# ENC_1_1.net
KiCad netlist of a schematic drawn in EAGLE
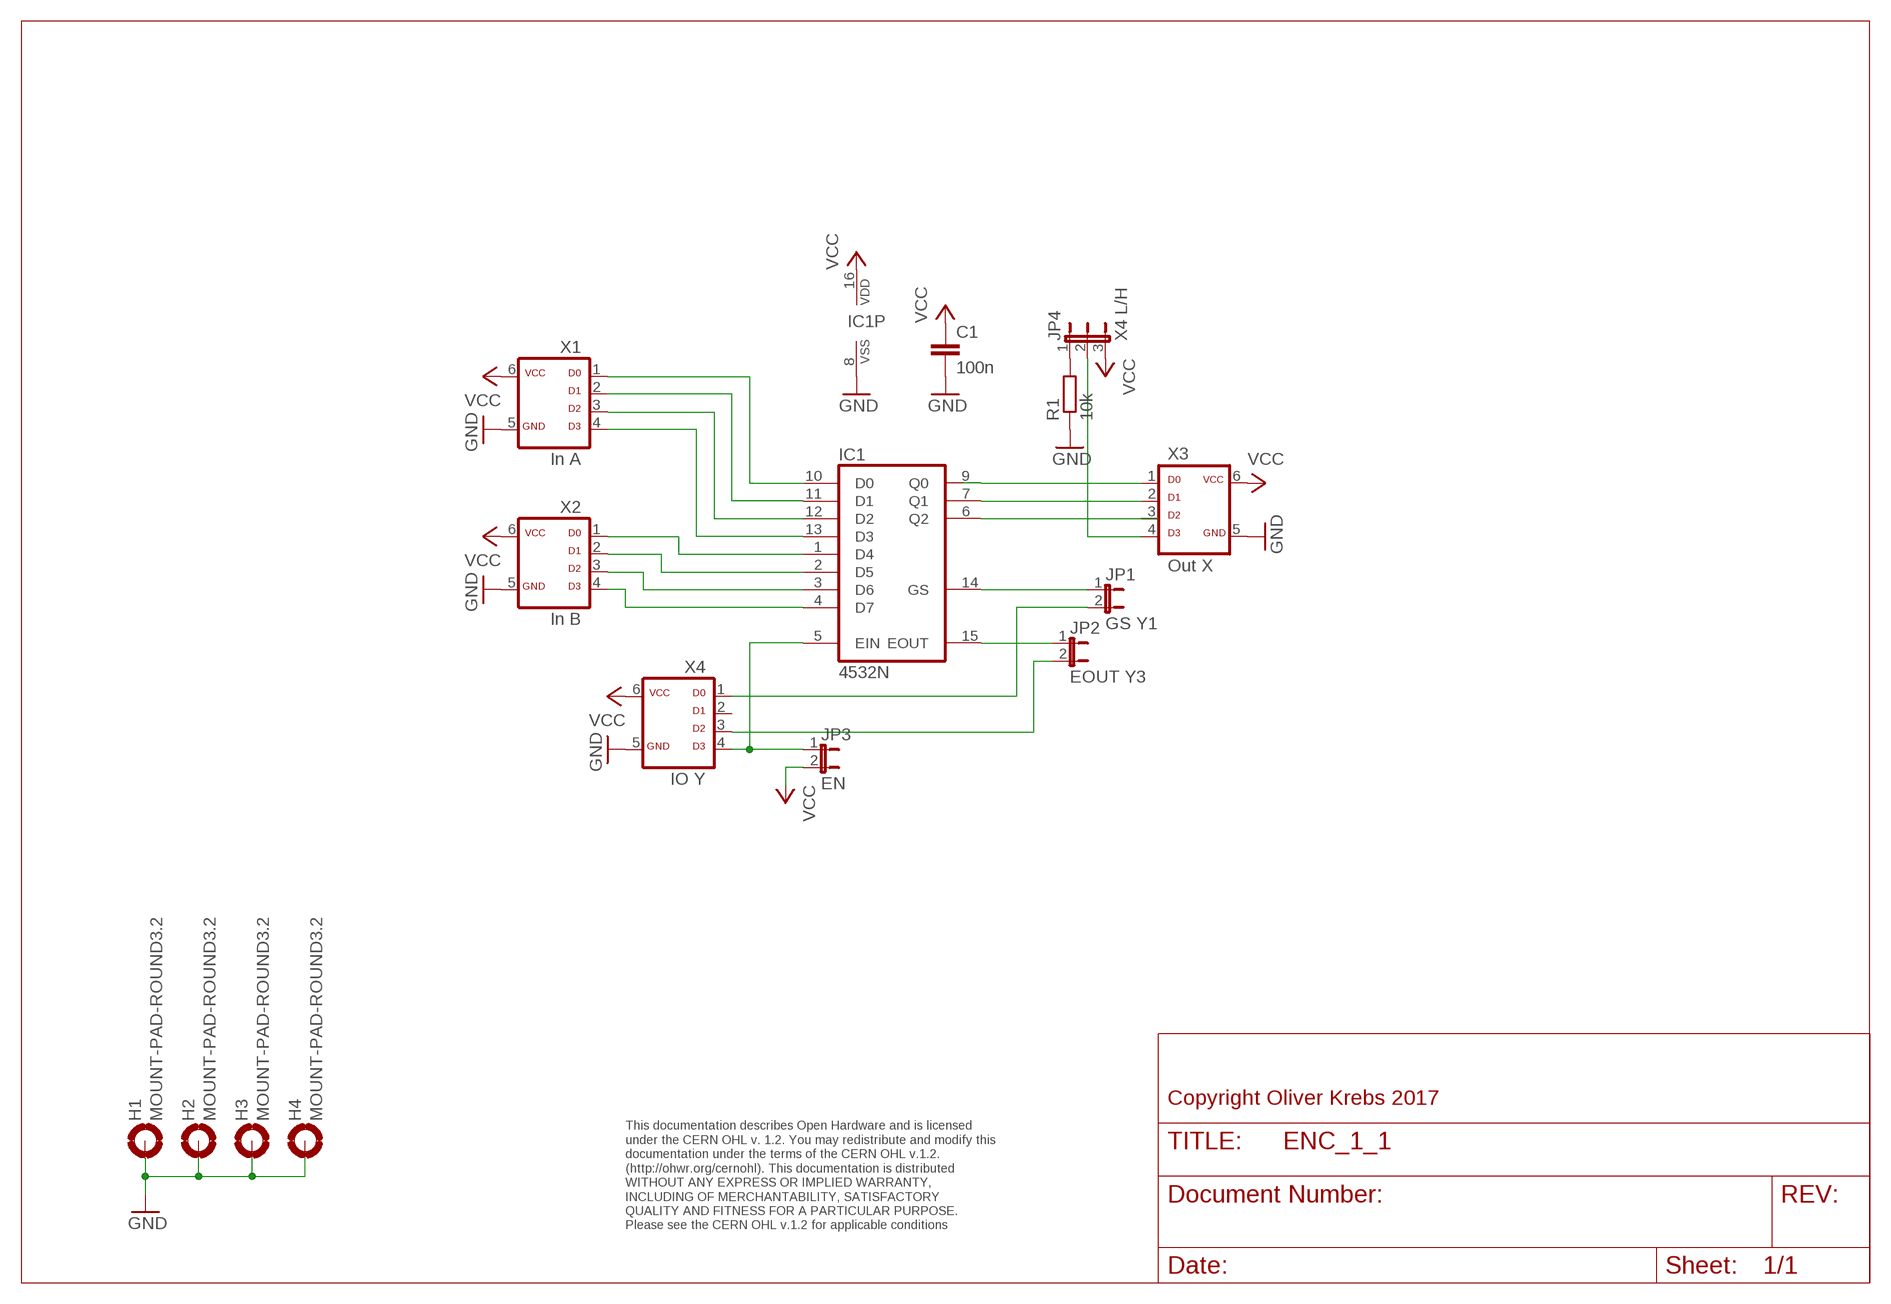
[diagram p0: schematic, sheet 1]

(export (version "E")
  (design (tool "Eeschema 10.0.6"))
  (components
    (comp (ref "C1")
      (value "100n")
      (footprint "eagle-import:C050-025X075")
      (libsource (lib "eagle-import") (part "C-EU050-025X075"))
    )
    (comp (ref "H1")
      (value "MOUNT-PAD-ROUND3.2")
      (footprint "eagle-import:3,2-PAD")
      (libsource (lib "eagle-import") (part "MOUNT-PAD-ROUND3.2"))
    )
    (comp (ref "H2")
      (value "MOUNT-PAD-ROUND3.2")
      (footprint "eagle-import:3,2-PAD")
      (libsource (lib "eagle-import") (part "MOUNT-PAD-ROUND3.2"))
    )
    (comp (ref "H3")
      (value "MOUNT-PAD-ROUND3.2")
      (footprint "eagle-import:3,2-PAD")
      (libsource (lib "eagle-import") (part "MOUNT-PAD-ROUND3.2"))
    )
    (comp (ref "H4")
      (value "MOUNT-PAD-ROUND3.2")
      (footprint "eagle-import:3,2-PAD")
      (libsource (lib "eagle-import") (part "MOUNT-PAD-ROUND3.2"))
    )
    (comp (ref "IC1")
      (value "4532N")
      (footprint "eagle-import:DIL16")
      (libsource (lib "eagle-import") (part "4532N"))
    )
    (comp (ref "JP1")
      (value "GS Y1")
      (footprint "eagle-import:JP1")
      (libsource (lib "eagle-import") (part "JP1E"))
    )
    (comp (ref "JP2")
      (value "EOUT Y3")
      (footprint "eagle-import:JP1")
      (libsource (lib "eagle-import") (part "JP1E"))
    )
    (comp (ref "JP3")
      (value "EN")
      (footprint "eagle-import:JP1")
      (libsource (lib "eagle-import") (part "JP1E"))
    )
    (comp (ref "JP4")
      (value "X4 L/H")
      (footprint "eagle-import:JP2-U")
      (libsource (lib "eagle-import") (part "JP2EJP2-U"))
    )
    (comp (ref "R1")
      (value "10k")
      (footprint "eagle-import:0207_10")
      (libsource (lib "eagle-import") (part "R-EU_0207/10"))
    )
    (comp (ref "X1")
      (value "In A")
      (footprint "eagle-import:ML-6")
      (libsource (lib "eagle-import") (part "ML6D"))
    )
    (comp (ref "X2")
      (value "In B")
      (footprint "eagle-import:ML-6")
      (libsource (lib "eagle-import") (part "ML6D"))
    )
    (comp (ref "X3")
      (value "Out X")
      (footprint "eagle-import:ML-6")
      (libsource (lib "eagle-import") (part "ML6D"))
    )
    (comp (ref "X4")
      (value "IO Y")
      (footprint "eagle-import:ML-6")
      (libsource (lib "eagle-import") (part "ML6D"))
    )
  )
  (nets
    (net (code "1") (name "GND") (class "Default")
      (node (ref "C1") (pin "2") (pinfunction "2_2") (pintype "passive"))
      (node (ref "H1") (pin "B3,2") (pinfunction "MOUNT_B3,2") (pintype "passive"))
      (node (ref "H2") (pin "B3,2") (pinfunction "MOUNT_B3,2") (pintype "passive"))
      (node (ref "H3") (pin "B3,2") (pinfunction "MOUNT_B3,2") (pintype "passive"))
      (node (ref "H4") (pin "B3,2") (pinfunction "MOUNT_B3,2") (pintype "passive"))
      (node (ref "IC1") (pin "8") (pinfunction "VSS_8") (pintype "power_in"))
      (node (ref "R1") (pin "1") (pinfunction "1_1") (pintype "passive"))
      (node (ref "X1") (pin "5") (pinfunction "5_5") (pintype "passive"))
      (node (ref "X2") (pin "5") (pinfunction "5_5") (pintype "passive"))
      (node (ref "X3") (pin "5") (pinfunction "5_5") (pintype "passive"))
      (node (ref "X4") (pin "5") (pinfunction "5_5") (pintype "passive"))
    )
    (net (code "2") (name "Net-(IC1A-D0)") (class "Default")
      (node (ref "IC1") (pin "10") (pinfunction "D0_10") (pintype "input"))
      (node (ref "X1") (pin "1") (pinfunction "1_1") (pintype "passive"))
    )
    (net (code "3") (name "Net-(IC1A-D1)") (class "Default")
      (node (ref "IC1") (pin "11") (pinfunction "D1_11") (pintype "input"))
      (node (ref "X1") (pin "2") (pinfunction "2_2") (pintype "passive"))
    )
    (net (code "4") (name "Net-(IC1A-D2)") (class "Default")
      (node (ref "IC1") (pin "12") (pinfunction "D2_12") (pintype "input"))
      (node (ref "X1") (pin "3") (pinfunction "3_3") (pintype "passive"))
    )
    (net (code "5") (name "Net-(IC1A-D3)") (class "Default")
      (node (ref "IC1") (pin "13") (pinfunction "D3_13") (pintype "input"))
      (node (ref "X1") (pin "4") (pinfunction "4_4") (pintype "passive"))
    )
    (net (code "6") (name "Net-(IC1A-D4)") (class "Default")
      (node (ref "IC1") (pin "1") (pinfunction "D4_1") (pintype "input"))
      (node (ref "X2") (pin "1") (pinfunction "1_1") (pintype "passive"))
    )
    (net (code "7") (name "Net-(IC1A-D5)") (class "Default")
      (node (ref "IC1") (pin "2") (pinfunction "D5_2") (pintype "input"))
      (node (ref "X2") (pin "2") (pinfunction "2_2") (pintype "passive"))
    )
    (net (code "8") (name "Net-(IC1A-D6)") (class "Default")
      (node (ref "IC1") (pin "3") (pinfunction "D6_3") (pintype "input"))
      (node (ref "X2") (pin "3") (pinfunction "3_3") (pintype "passive"))
    )
    (net (code "9") (name "Net-(IC1A-D7)") (class "Default")
      (node (ref "IC1") (pin "4") (pinfunction "D7_4") (pintype "input"))
      (node (ref "X2") (pin "4") (pinfunction "4_4") (pintype "passive"))
    )
    (net (code "10") (name "Net-(IC1A-EIN)") (class "Default")
      (node (ref "IC1") (pin "5") (pinfunction "EIN_5") (pintype "input"))
      (node (ref "JP3") (pin "1") (pinfunction "1_1") (pintype "passive"))
      (node (ref "X4") (pin "4") (pinfunction "4_4") (pintype "passive"))
    )
    (net (code "11") (name "Net-(IC1A-EOUT)") (class "Default")
      (node (ref "IC1") (pin "15") (pinfunction "EOUT_15") (pintype "output"))
      (node (ref "JP2") (pin "1") (pinfunction "1_1") (pintype "passive"))
    )
    (net (code "12") (name "Net-(IC1A-GS)") (class "Default")
      (node (ref "IC1") (pin "14") (pinfunction "GS_14") (pintype "output"))
      (node (ref "JP1") (pin "1") (pinfunction "1_1") (pintype "passive"))
    )
    (net (code "13") (name "Net-(IC1A-Q0)") (class "Default")
      (node (ref "IC1") (pin "9") (pinfunction "Q0_9") (pintype "output"))
      (node (ref "X3") (pin "1") (pinfunction "1_1") (pintype "passive"))
    )
    (net (code "14") (name "Net-(IC1A-Q1)") (class "Default")
      (node (ref "IC1") (pin "7") (pinfunction "Q1_7") (pintype "output"))
      (node (ref "X3") (pin "2") (pinfunction "2_2") (pintype "passive"))
    )
    (net (code "15") (name "Net-(IC1A-Q2)") (class "Default")
      (node (ref "IC1") (pin "6") (pinfunction "Q2_6") (pintype "output"))
      (node (ref "X3") (pin "3") (pinfunction "3_3") (pintype "passive"))
    )
    (net (code "16") (name "Net-(JP1-Pad2)") (class "Default")
      (node (ref "JP1") (pin "2") (pinfunction "2_2") (pintype "passive"))
      (node (ref "X4") (pin "1") (pinfunction "1_1") (pintype "passive"))
    )
    (net (code "17") (name "Net-(JP2-Pad2)") (class "Default")
      (node (ref "JP2") (pin "2") (pinfunction "2_2") (pintype "passive"))
      (node (ref "X4") (pin "3") (pinfunction "3_3") (pintype "passive"))
    )
    (net (code "18") (name "Net-(JP4-Pad1)") (class "Default")
      (node (ref "JP4") (pin "1") (pinfunction "1_1") (pintype "passive"))
      (node (ref "R1") (pin "2") (pinfunction "2_2") (pintype "passive"))
    )
    (net (code "19") (name "Net-(JP4-Pad2)") (class "Default")
      (node (ref "JP4") (pin "2") (pinfunction "2_2") (pintype "passive"))
      (node (ref "X3") (pin "4") (pinfunction "4_4") (pintype "passive"))
    )
    (net (code "20") (name "VCC") (class "Default")
      (node (ref "C1") (pin "1") (pinfunction "1_1") (pintype "passive"))
      (node (ref "IC1") (pin "16") (pinfunction "VDD_16") (pintype "power_in"))
      (node (ref "JP3") (pin "2") (pinfunction "2_2") (pintype "passive"))
      (node (ref "JP4") (pin "3") (pinfunction "3_3") (pintype "passive"))
      (node (ref "X1") (pin "6") (pinfunction "6_6") (pintype "passive"))
      (node (ref "X2") (pin "6") (pinfunction "6_6") (pintype "passive"))
      (node (ref "X3") (pin "6") (pinfunction "6_6") (pintype "passive"))
      (node (ref "X4") (pin "6") (pinfunction "6_6") (pintype "passive"))
    )
    (net (code "21") (name "unconnected-(X4-Pad2)") (class "Default")
      (node (ref "X4") (pin "2") (pinfunction "2_2") (pintype "passive"))
    )
  )
)
